# GSv1_schematic.net
KiCad netlist of a schematic drawn in Altium Designer
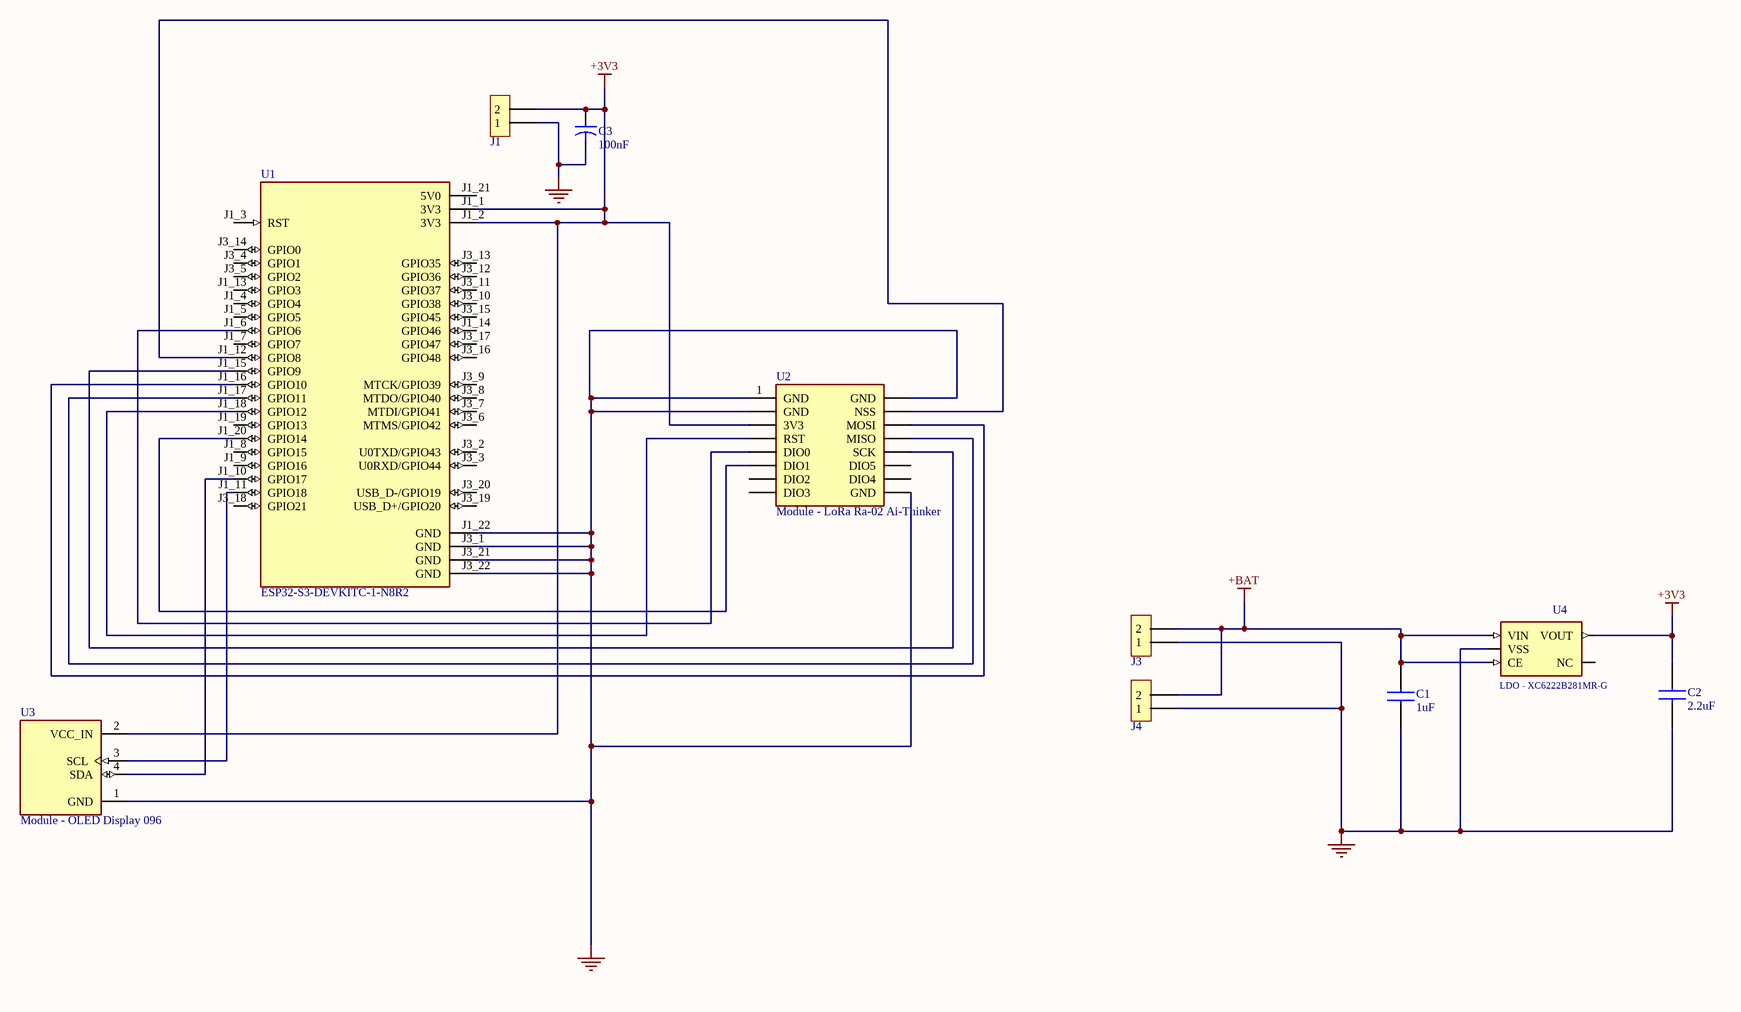
[diagram p0: GSv1_schematic.SchDoc]

(export (version "E")
  (design (tool "Eeschema 10.0.6"))
  (components
    (comp (ref "C1")
      (value "1uF")
      (footprint "0805")
      (description "SMD Ceramic Capacitor")
      (libsource (lib "Passive_Devices") (part "CAP - SMD_0805(inch)"))
    )
    (comp (ref "C2")
      (value "2.2uF")
      (footprint "0805")
      (description "SMD Ceramic Capacitor")
      (libsource (lib "Passive_Devices") (part "CAP - SMD_0805(inch)"))
    )
    (comp (ref "C3")
      (value "100nF")
      (footprint "DIP_Electrolytic_Capacitor")
      (description "Capacitor")
      (fields
        (field (name "Comment") "DIP - Electrolytic Capacitor")
        (field (name "PUBLISHER") "Altium Limited")
      )
      (libsource (lib "Passive_Devices") (part "DIP - Electrolytic Capacitor"))
    )
    (comp (ref "J1")
      (value "J - Header 2.54mm 2Pos 1Row")
      (footprint "Header 2.54mm 2Pos 1Row")
      (fields (field (name "PUBLISHER") "Altium Limited"))
      (libsource (lib "Connectors_PLUS_headers") (part "J - Header 2.54mm 2Pos 1Row"))
    )
    (comp (ref "J3")
      (value "J - Header 2.54mm 2Pos 1Row")
      (footprint "Header 2.54mm 2Pos 1Row")
      (fields (field (name "PUBLISHER") "Altium Limited"))
      (libsource (lib "Connectors_PLUS_headers") (part "J - Header 2.54mm 2Pos 1Row"))
    )
    (comp (ref "J4")
      (value "J - Connector 5.08mm 2Pos")
      (footprint "CONNECTOR 508mm 2POS")
      (libsource (lib "Connectors_PLUS_headers") (part "J - Connector 5.08mm 2Pos"))
    )
    (comp (ref "U1")
      (value "ESP32-S3-DEVKITC-1-N8R2")
      (footprint "ORIGINAL_ESP32-S3-DEVKITC_1")
      (fields (field (name "MF") "Espressif Systems"))
      (libsource (lib "Devices_SMD_plus_DIP") (part "ESP32-S3-DEVKITC-1-N8R2"))
    )
    (comp (ref "U2")
      (value "Module - LoRa Ra-02 Ai-Thinker")
      (footprint "MODULE LoRa Ra-02 Ai Thinker_separate rows")
      (description "LoRa 433 MHz Module")
      (libsource (lib "Devices_SMD_plus_DIP") (part "Module - LoRa Ra-02 Ai-Thinker"))
    )
    (comp (ref "U3")
      (value "Module - OLED Display 096")
      (footprint "MODULE_DM-OLED096-636")
      (description "0.96â€ 128 X 64 MONOCHROME GRAPHIC OLED DISPLAY MODULE - I2C")
      (libsource (lib "Devices_SMD_plus_DIP") (part "Module - OLED Display 096"))
    )
    (comp (ref "U4")
      (value "LDO - XC6222B281MR-G")
      (footprint "Devices_SMD_plus_DIP:SOT25")
      (description "Linear Voltage Regulator IC 1 Output 700mA SOT-25")
      (fields (field (name "MF") "Torex") (field (name "MP") "XC6222B281MR-G"))
      (libsource (lib "Devices_SMD_plus_DIP") (part "LDO - XC6222B281MR-G"))
    )
  )
  (nets
    (net (code "1") (name "+3V3") (class "Default")
      (node (ref "C2") (pin "2") (pinfunction "2_2") (pintype "passive"))
      (node (ref "C3") (pin "1") (pinfunction "1_1") (pintype "passive"))
      (node (ref "J1") (pin "2") (pinfunction "2_2") (pintype "passive"))
      (node (ref "U1") (pin "J1_1") (pinfunction "3V3_J1_1") (pintype "power_in"))
      (node (ref "U1") (pin "J1_2") (pinfunction "3V3_J1_2") (pintype "power_in"))
      (node (ref "U2") (pin "3") (pinfunction "3V3_3") (pintype "passive"))
      (node (ref "U3") (pin "2") (pinfunction "VCC_IN_2") (pintype "power_in"))
      (node (ref "U4") (pin "P$4") (pinfunction "VOUT_P$4") (pintype "output"))
    )
    (net (code "2") (name "+BAT") (class "Default")
      (node (ref "C1") (pin "2") (pinfunction "2_2") (pintype "passive"))
      (node (ref "J3") (pin "2") (pinfunction "2_2") (pintype "passive"))
      (node (ref "J4") (pin "2") (pinfunction "2_2") (pintype "passive"))
      (node (ref "U4") (pin "P$1") (pinfunction "VIN_P$1") (pintype "input"))
      (node (ref "U4") (pin "P$3") (pinfunction "CE_P$3") (pintype "input"))
    )
    (net (code "3") (name "GND") (class "Default")
      (node (ref "C1") (pin "1") (pinfunction "1_1") (pintype "passive"))
      (node (ref "C2") (pin "1") (pinfunction "1_1") (pintype "passive"))
      (node (ref "C3") (pin "2") (pinfunction "2_2") (pintype "passive"))
      (node (ref "J1") (pin "1") (pinfunction "1_1") (pintype "passive"))
      (node (ref "J3") (pin "1") (pinfunction "1_1") (pintype "passive"))
      (node (ref "J4") (pin "1") (pinfunction "1_1") (pintype "passive"))
      (node (ref "U1") (pin "J1_22") (pinfunction "GND_J1_22") (pintype "power_in"))
      (node (ref "U1") (pin "J3_1") (pinfunction "GND_J3_1") (pintype "power_in"))
      (node (ref "U1") (pin "J3_21") (pinfunction "GND_J3_21") (pintype "power_in"))
      (node (ref "U1") (pin "J3_22") (pinfunction "GND_J3_22") (pintype "power_in"))
      (node (ref "U2") (pin "1") (pinfunction "GND_1") (pintype "passive"))
      (node (ref "U2") (pin "16") (pinfunction "GND_16") (pintype "passive"))
      (node (ref "U2") (pin "2") (pinfunction "GND_2") (pintype "passive"))
      (node (ref "U2") (pin "9") (pinfunction "GND_9") (pintype "passive"))
      (node (ref "U3") (pin "1") (pinfunction "GND_1") (pintype "power_in"))
      (node (ref "U4") (pin "P$2") (pinfunction "VSS_P$2") (pintype "power_in"))
    )
    (net (code "4") (name "Net-(U1-GPIO6)") (class "Default")
      (node (ref "U1") (pin "J1_6") (pinfunction "GPIO6_J1_6") (pintype "bidirectional"))
      (node (ref "U2") (pin "5") (pinfunction "DIO0_5") (pintype "passive"))
    )
    (net (code "5") (name "Net-(U1-GPIO8)") (class "Default")
      (node (ref "U1") (pin "J1_12") (pinfunction "GPIO8_J1_12") (pintype "bidirectional"))
      (node (ref "U2") (pin "10") (pinfunction "NSS_10") (pintype "passive"))
    )
    (net (code "6") (name "Net-(U1-GPIO9)") (class "Default")
      (node (ref "U1") (pin "J1_15") (pinfunction "GPIO9_J1_15") (pintype "bidirectional"))
      (node (ref "U2") (pin "13") (pinfunction "SCK_13") (pintype "passive"))
    )
    (net (code "7") (name "Net-(U1-GPIO10)") (class "Default")
      (node (ref "U1") (pin "J1_16") (pinfunction "GPIO10_J1_16") (pintype "bidirectional"))
      (node (ref "U2") (pin "11") (pinfunction "MOSI_11") (pintype "passive"))
    )
    (net (code "8") (name "Net-(U1-GPIO11)") (class "Default")
      (node (ref "U1") (pin "J1_17") (pinfunction "GPIO11_J1_17") (pintype "bidirectional"))
      (node (ref "U2") (pin "12") (pinfunction "MISO_12") (pintype "passive"))
    )
    (net (code "9") (name "Net-(U1-GPIO12)") (class "Default")
      (node (ref "U1") (pin "J1_18") (pinfunction "GPIO12_J1_18") (pintype "bidirectional"))
      (node (ref "U2") (pin "4") (pinfunction "RST_4") (pintype "passive"))
    )
    (net (code "10") (name "Net-(U1-GPIO14)") (class "Default")
      (node (ref "U1") (pin "J1_20") (pinfunction "GPIO14_J1_20") (pintype "bidirectional"))
      (node (ref "U2") (pin "6") (pinfunction "DIO1_6") (pintype "passive"))
    )
    (net (code "11") (name "Net-(U1-GPIO17)") (class "Default")
      (node (ref "U1") (pin "J1_10") (pinfunction "GPIO17_J1_10") (pintype "bidirectional"))
      (node (ref "U3") (pin "4") (pinfunction "SDA_4") (pintype "bidirectional"))
    )
    (net (code "12") (name "Net-(U1-GPIO18)") (class "Default")
      (node (ref "U1") (pin "J1_11") (pinfunction "GPIO18_J1_11") (pintype "bidirectional"))
      (node (ref "U3") (pin "3") (pinfunction "SCL_3") (pintype "input"))
    )
    (net (code "13") (name "unconnected-(U1-5V0-PadJ1_21)") (class "Default")
      (node (ref "U1") (pin "J1_21") (pinfunction "5V0_J1_21") (pintype "power_in"))
    )
    (net (code "14") (name "unconnected-(U1-GPIO0-PadJ3_14)") (class "Default")
      (node (ref "U1") (pin "J3_14") (pinfunction "GPIO0_J3_14") (pintype "bidirectional"))
    )
    (net (code "15") (name "unconnected-(U1-GPIO1-PadJ3_4)") (class "Default")
      (node (ref "U1") (pin "J3_4") (pinfunction "GPIO1_J3_4") (pintype "bidirectional"))
    )
    (net (code "16") (name "unconnected-(U1-GPIO2-PadJ3_5)") (class "Default")
      (node (ref "U1") (pin "J3_5") (pinfunction "GPIO2_J3_5") (pintype "bidirectional"))
    )
    (net (code "17") (name "unconnected-(U1-GPIO3-PadJ1_13)") (class "Default")
      (node (ref "U1") (pin "J1_13") (pinfunction "GPIO3_J1_13") (pintype "bidirectional"))
    )
    (net (code "18") (name "unconnected-(U1-GPIO4-PadJ1_4)") (class "Default")
      (node (ref "U1") (pin "J1_4") (pinfunction "GPIO4_J1_4") (pintype "bidirectional"))
    )
    (net (code "19") (name "unconnected-(U1-GPIO5-PadJ1_5)") (class "Default")
      (node (ref "U1") (pin "J1_5") (pinfunction "GPIO5_J1_5") (pintype "bidirectional"))
    )
    (net (code "20") (name "unconnected-(U1-GPIO7-PadJ1_7)") (class "Default")
      (node (ref "U1") (pin "J1_7") (pinfunction "GPIO7_J1_7") (pintype "bidirectional"))
    )
    (net (code "21") (name "unconnected-(U1-GPIO13-PadJ1_19)") (class "Default")
      (node (ref "U1") (pin "J1_19") (pinfunction "GPIO13_J1_19") (pintype "bidirectional"))
    )
    (net (code "22") (name "unconnected-(U1-GPIO15-PadJ1_8)") (class "Default")
      (node (ref "U1") (pin "J1_8") (pinfunction "GPIO15_J1_8") (pintype "bidirectional"))
    )
    (net (code "23") (name "unconnected-(U1-GPIO16-PadJ1_9)") (class "Default")
      (node (ref "U1") (pin "J1_9") (pinfunction "GPIO16_J1_9") (pintype "bidirectional"))
    )
    (net (code "24") (name "unconnected-(U1-GPIO21-PadJ3_18)") (class "Default")
      (node (ref "U1") (pin "J3_18") (pinfunction "GPIO21_J3_18") (pintype "bidirectional"))
    )
    (net (code "25") (name "unconnected-(U1-GPIO35-PadJ3_13)") (class "Default")
      (node (ref "U1") (pin "J3_13") (pinfunction "GPIO35_J3_13") (pintype "bidirectional"))
    )
    (net (code "26") (name "unconnected-(U1-GPIO36-PadJ3_12)") (class "Default")
      (node (ref "U1") (pin "J3_12") (pinfunction "GPIO36_J3_12") (pintype "bidirectional"))
    )
    (net (code "27") (name "unconnected-(U1-GPIO37-PadJ3_11)") (class "Default")
      (node (ref "U1") (pin "J3_11") (pinfunction "GPIO37_J3_11") (pintype "bidirectional"))
    )
    (net (code "28") (name "unconnected-(U1-GPIO38-PadJ3_10)") (class "Default")
      (node (ref "U1") (pin "J3_10") (pinfunction "GPIO38_J3_10") (pintype "bidirectional"))
    )
    (net (code "29") (name "unconnected-(U1-GPIO45-PadJ3_15)") (class "Default")
      (node (ref "U1") (pin "J3_15") (pinfunction "GPIO45_J3_15") (pintype "bidirectional"))
    )
    (net (code "30") (name "unconnected-(U1-GPIO46-PadJ1_14)") (class "Default")
      (node (ref "U1") (pin "J1_14") (pinfunction "GPIO46_J1_14") (pintype "bidirectional"))
    )
    (net (code "31") (name "unconnected-(U1-GPIO47-PadJ3_17)") (class "Default")
      (node (ref "U1") (pin "J3_17") (pinfunction "GPIO47_J3_17") (pintype "bidirectional"))
    )
    (net (code "32") (name "unconnected-(U1-GPIO48-PadJ3_16)") (class "Default")
      (node (ref "U1") (pin "J3_16") (pinfunction "GPIO48_J3_16") (pintype "bidirectional"))
    )
    (net (code "33") (name "unconnected-(U1-MTCK{slash}GPIO39-PadJ3_9)") (class "Default")
      (node (ref "U1") (pin "J3_9") (pinfunction "MTCK/GPIO39_J3_9") (pintype "bidirectional"))
    )
    (net (code "34") (name "unconnected-(U1-MTDI{slash}GPIO41-PadJ3_7)") (class "Default")
      (node (ref "U1") (pin "J3_7") (pinfunction "MTDI/GPIO41_J3_7") (pintype "bidirectional"))
    )
    (net (code "35") (name "unconnected-(U1-MTDO{slash}GPIO40-PadJ3_8)") (class "Default")
      (node (ref "U1") (pin "J3_8") (pinfunction "MTDO/GPIO40_J3_8") (pintype "bidirectional"))
    )
    (net (code "36") (name "unconnected-(U1-MTMS{slash}GPIO42-PadJ3_6)") (class "Default")
      (node (ref "U1") (pin "J3_6") (pinfunction "MTMS/GPIO42_J3_6") (pintype "bidirectional"))
    )
    (net (code "37") (name "unconnected-(U1-RST-PadJ1_3)") (class "Default")
      (node (ref "U1") (pin "J1_3") (pinfunction "RST_J1_3") (pintype "input"))
    )
    (net (code "38") (name "unconnected-(U1-U0RXD{slash}GPIO44-PadJ3_3)") (class "Default")
      (node (ref "U1") (pin "J3_3") (pinfunction "U0RXD/GPIO44_J3_3") (pintype "bidirectional"))
    )
    (net (code "39") (name "unconnected-(U1-U0TXD{slash}GPIO43-PadJ3_2)") (class "Default")
      (node (ref "U1") (pin "J3_2") (pinfunction "U0TXD/GPIO43_J3_2") (pintype "bidirectional"))
    )
    (net (code "40") (name "unconnected-(U1-USB_D+{slash}GPIO20-PadJ3_19)") (class "Default")
      (node (ref "U1") (pin "J3_19") (pinfunction "USB_D+/GPIO20_J3_19") (pintype "bidirectional"))
    )
    (net (code "41") (name "unconnected-(U1-USB_D-{slash}GPIO19-PadJ3_20)") (class "Default")
      (node (ref "U1") (pin "J3_20") (pinfunction "USB_D-/GPIO19_J3_20") (pintype "bidirectional"))
    )
    (net (code "42") (name "unconnected-(U2-DIO2-Pad7)") (class "Default")
      (node (ref "U2") (pin "7") (pinfunction "DIO2_7") (pintype "passive"))
    )
    (net (code "43") (name "unconnected-(U2-DIO3-Pad8)") (class "Default")
      (node (ref "U2") (pin "8") (pinfunction "DIO3_8") (pintype "passive"))
    )
    (net (code "44") (name "unconnected-(U2-DIO4-Pad15)") (class "Default")
      (node (ref "U2") (pin "15") (pinfunction "DIO4_15") (pintype "passive"))
    )
    (net (code "45") (name "unconnected-(U2-DIO5-Pad14)") (class "Default")
      (node (ref "U2") (pin "14") (pinfunction "DIO5_14") (pintype "passive"))
    )
    (net (code "46") (name "unconnected-(U4-NC-PadP$5)") (class "Default")
      (node (ref "U4") (pin "P$5") (pinfunction "NC_P$5") (pintype "bidirectional"))
    )
  )
)
